# Debug.net
KiCad netlist of a schematic drawn in EAGLE
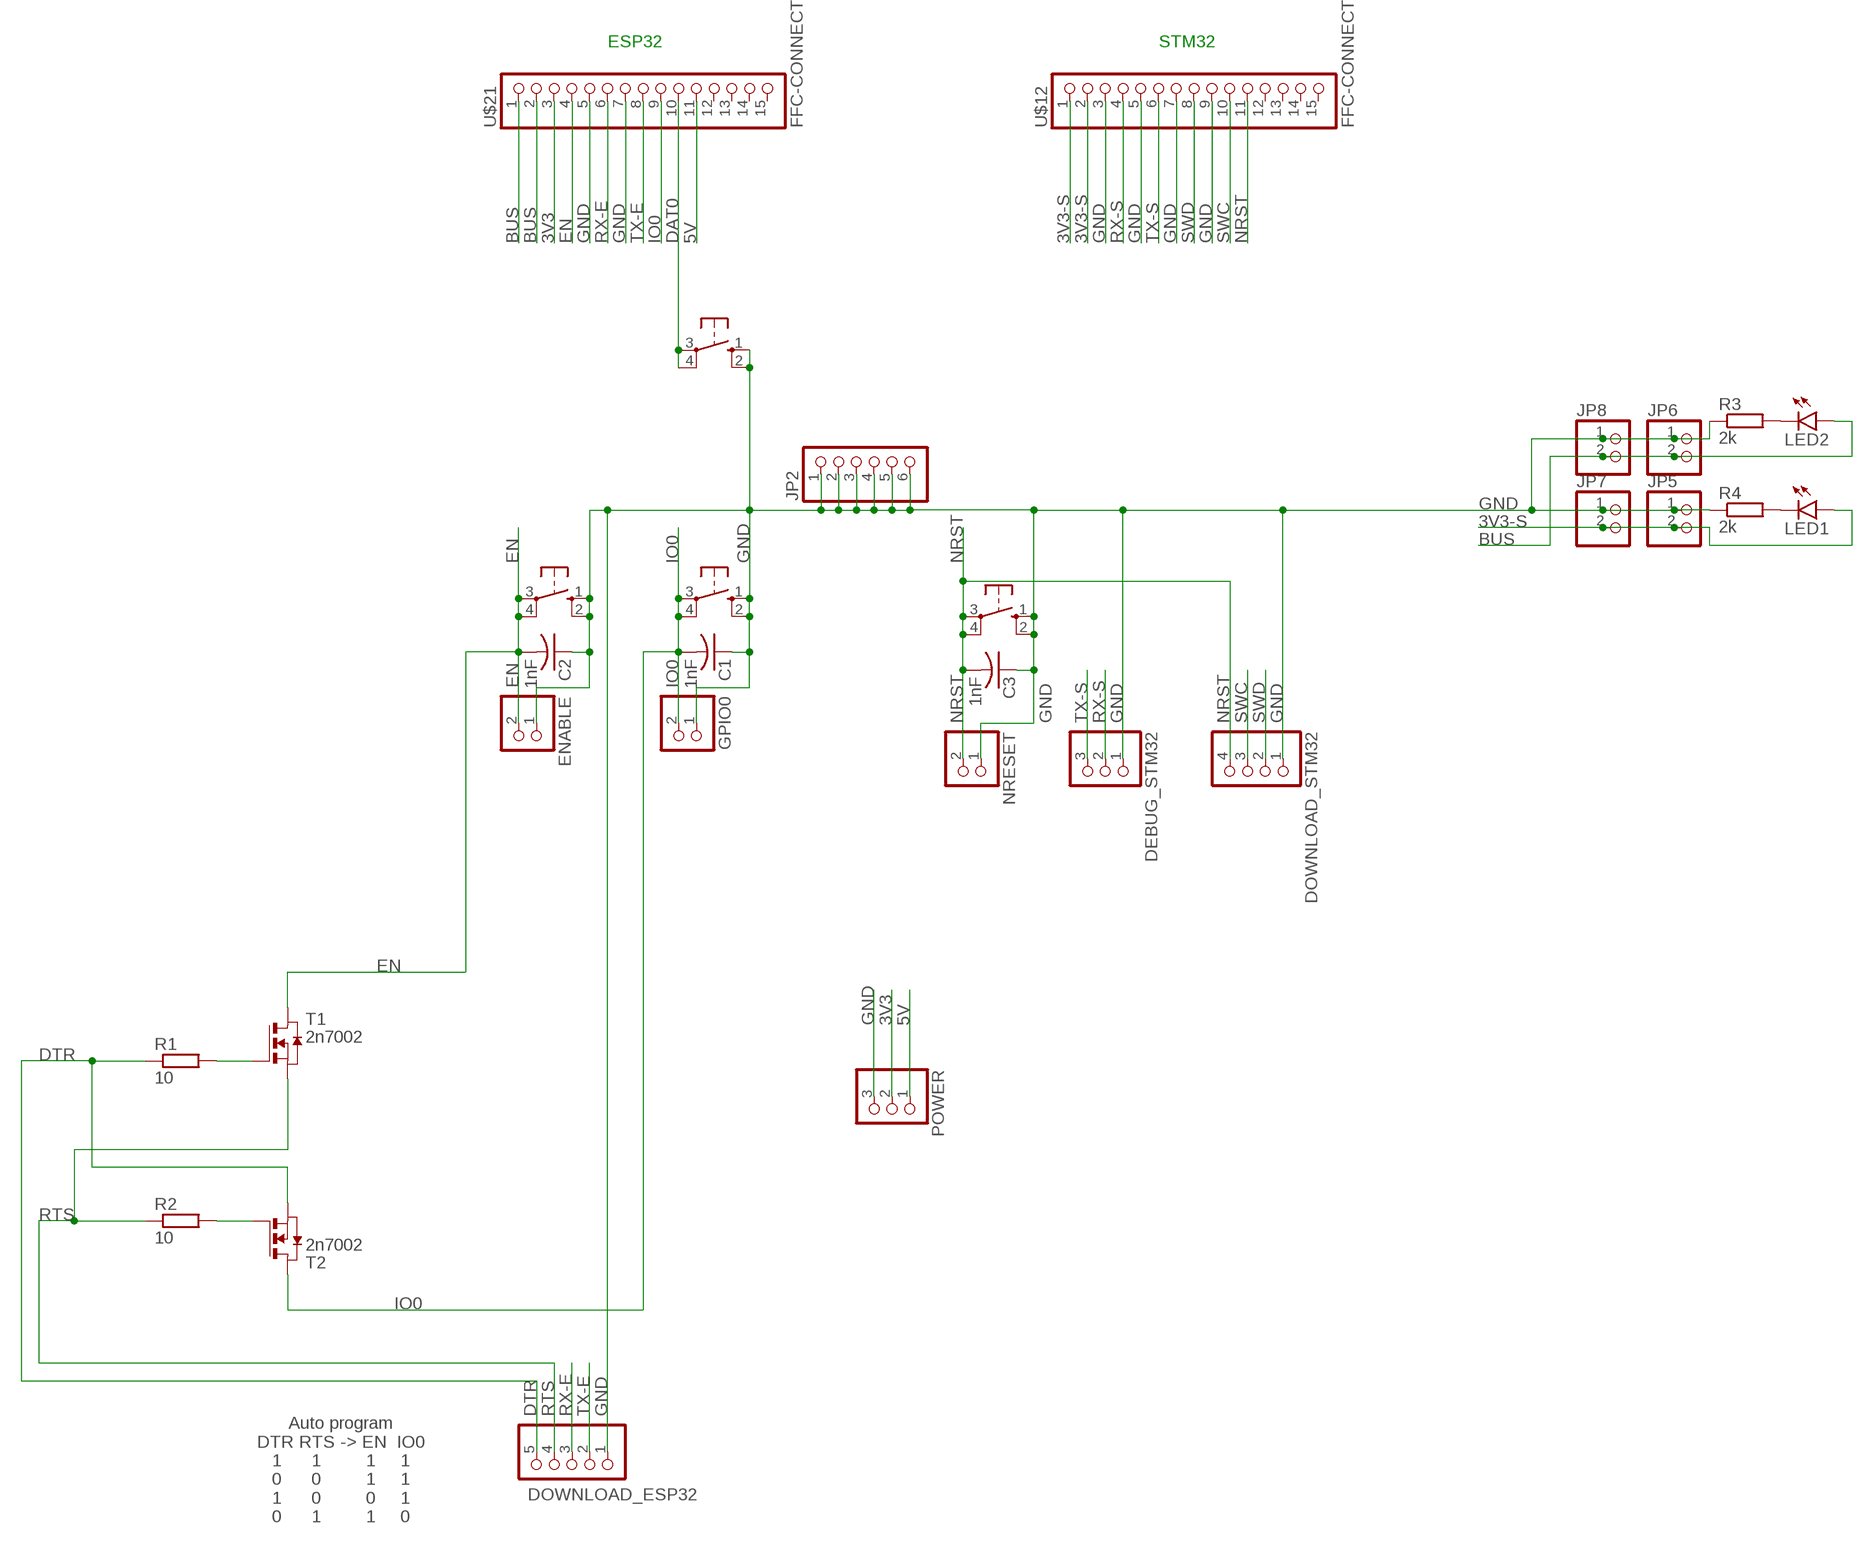
[diagram p0: schematic, sheet 1]

(export (version "E")
  (design (tool "Eeschema 10.0.6"))
  (components
    (comp (ref "C1")
      (value "1nF")
      (footprint "eagle-import:C0603")
      (libsource (lib "eagle-import") (part "C-USC0603"))
    )
    (comp (ref "C2")
      (value "1nF")
      (footprint "eagle-import:C0603")
      (libsource (lib "eagle-import") (part "C-USC0603"))
    )
    (comp (ref "C3")
      (value "1nF")
      (footprint "eagle-import:C0603")
      (libsource (lib "eagle-import") (part "C-USC0603"))
    )
    (comp (ref "DAT0")
      (value "10-XX")
      (footprint "eagle-import:B3F-10XX")
      (fields (field (name "MPN") "B3F-1000"))
      (libsource (lib "eagle-import") (part "10-XX"))
    )
    (comp (ref "DEBUG_STM32")
      (value "PINHD-1X3")
      (footprint "eagle-import:1X03")
      (libsource (lib "eagle-import") (part "PINHD-1X3"))
    )
    (comp (ref "DOWNLOAD_ESP32")
      (value "PINHD-1X5")
      (footprint "eagle-import:1X05")
      (libsource (lib "eagle-import") (part "PINHD-1X5"))
    )
    (comp (ref "DOWNLOAD_STM32")
      (value "PINHD-1X4")
      (footprint "eagle-import:1X04")
      (libsource (lib "eagle-import") (part "PINHD-1X4"))
    )
    (comp (ref "EN")
      (value "10-XX")
      (footprint "eagle-import:B3F-10XX")
      (fields (field (name "MPN") "B3F-1000"))
      (libsource (lib "eagle-import") (part "10-XX"))
    )
    (comp (ref "ENABLE")
      (value "PINHD-1X2")
      (footprint "eagle-import:1X02")
      (libsource (lib "eagle-import") (part "PINHD-1X2"))
    )
    (comp (ref "GPIO0")
      (value "PINHD-1X2")
      (footprint "eagle-import:1X02")
      (libsource (lib "eagle-import") (part "PINHD-1X2"))
    )
    (comp (ref "IO0")
      (value "10-XX")
      (footprint "eagle-import:B3F-10XX")
      (fields (field (name "MPN") "B3F-1000"))
      (libsource (lib "eagle-import") (part "10-XX"))
    )
    (comp (ref "JP2")
      (value "PINHD-1X6")
      (footprint "eagle-import:1X06")
      (libsource (lib "eagle-import") (part "PINHD-1X6"))
    )
    (comp (ref "JP5")
      (value "PINHD-1X2")
      (footprint "eagle-import:1X02")
      (libsource (lib "eagle-import") (part "PINHD-1X2"))
    )
    (comp (ref "JP6")
      (value "PINHD-1X2")
      (footprint "eagle-import:1X02")
      (libsource (lib "eagle-import") (part "PINHD-1X2"))
    )
    (comp (ref "JP7")
      (value "PINHD-1X2")
      (footprint "eagle-import:1X02")
      (libsource (lib "eagle-import") (part "PINHD-1X2"))
    )
    (comp (ref "JP8")
      (value "PINHD-1X2")
      (footprint "eagle-import:1X02")
      (libsource (lib "eagle-import") (part "PINHD-1X2"))
    )
    (comp (ref "LED1")
      (value "LEDCHIPLED_0603")
      (footprint "eagle-import:CHIPLED_0603")
      (libsource (lib "eagle-import") (part "LEDCHIPLED_0603"))
    )
    (comp (ref "LED2")
      (value "LEDCHIPLED_0603")
      (footprint "eagle-import:CHIPLED_0603")
      (libsource (lib "eagle-import") (part "LEDCHIPLED_0603"))
    )
    (comp (ref "NRESET")
      (value "PINHD-1X2")
      (footprint "eagle-import:1X02")
      (libsource (lib "eagle-import") (part "PINHD-1X2"))
    )
    (comp (ref "NRST")
      (value "10-XX")
      (footprint "eagle-import:B3F-10XX")
      (fields (field (name "MPN") "B3F-1000"))
      (libsource (lib "eagle-import") (part "10-XX"))
    )
    (comp (ref "POWER")
      (value "PINHD-1X3")
      (footprint "eagle-import:1X03")
      (libsource (lib "eagle-import") (part "PINHD-1X3"))
    )
    (comp (ref "R1")
      (value "10")
      (footprint "eagle-import:R0603")
      (libsource (lib "eagle-import") (part "R-EU_R0603"))
    )
    (comp (ref "R2")
      (value "10")
      (footprint "eagle-import:R0603")
      (libsource (lib "eagle-import") (part "R-EU_R0603"))
    )
    (comp (ref "R3")
      (value "2k")
      (footprint "eagle-import:R0603")
      (libsource (lib "eagle-import") (part "R-EU_R0603"))
    )
    (comp (ref "R4")
      (value "2k")
      (footprint "eagle-import:R0603")
      (libsource (lib "eagle-import") (part "R-EU_R0603"))
    )
    (comp (ref "T1")
      (value "2n7002")
      (footprint "eagle-import:SOT-23")
      (libsource (lib "eagle-import") (part "NMOSSOT23"))
    )
    (comp (ref "T2")
      (value "2n7002")
      (footprint "eagle-import:SOT-23")
      (libsource (lib "eagle-import") (part "NMOSSOT23"))
    )
    (comp (ref "U$12")
      (value "FFC-CONNECT")
      (footprint "eagle-import:SLW15S")
      (libsource (lib "eagle-import") (part "FFC-CONNECT"))
    )
    (comp (ref "U$21")
      (value "FFC-CONNECT")
      (footprint "eagle-import:SLW15S")
      (libsource (lib "eagle-import") (part "FFC-CONNECT"))
    )
  )
  (nets
    (net (code "1") (name "/3V3") (class "Default")
      (node (ref "POWER") (pin "2") (pinfunction "2_2") (pintype "passive"))
      (node (ref "U$21") (pin "3") (pinfunction "3_3") (pintype "passive"))
    )
    (net (code "2") (name "/3V3-S") (class "Default")
      (node (ref "JP5") (pin "2") (pinfunction "2_2") (pintype "passive"))
      (node (ref "JP7") (pin "2") (pinfunction "2_2") (pintype "passive"))
      (node (ref "LED1") (pin "A") (pinfunction "A_A") (pintype "passive"))
      (node (ref "U$12") (pin "1") (pinfunction "1_1") (pintype "passive"))
      (node (ref "U$12") (pin "2") (pinfunction "2_2") (pintype "passive"))
    )
    (net (code "3") (name "/5V") (class "Default")
      (node (ref "POWER") (pin "1") (pinfunction "1_1") (pintype "passive"))
      (node (ref "U$21") (pin "11") (pinfunction "11_11") (pintype "passive"))
    )
    (net (code "4") (name "/BUS") (class "Default")
      (node (ref "JP6") (pin "2") (pinfunction "2_2") (pintype "passive"))
      (node (ref "JP8") (pin "2") (pinfunction "2_2") (pintype "passive"))
      (node (ref "LED2") (pin "A") (pinfunction "A_A") (pintype "passive"))
      (node (ref "U$21") (pin "1") (pinfunction "1_1") (pintype "passive"))
      (node (ref "U$21") (pin "2") (pinfunction "2_2") (pintype "passive"))
    )
    (net (code "5") (name "/DAT0") (class "Default")
      (node (ref "DAT0") (pin "3") (pinfunction "P_3") (pintype "passive"))
      (node (ref "DAT0") (pin "4") (pinfunction "P1_4") (pintype "passive"))
      (node (ref "U$21") (pin "10") (pinfunction "10_10") (pintype "passive"))
    )
    (net (code "6") (name "/DTR") (class "Default")
      (node (ref "DOWNLOAD_ESP32") (pin "5") (pinfunction "5_5") (pintype "passive"))
      (node (ref "R1") (pin "1") (pinfunction "1_1") (pintype "passive"))
      (node (ref "T2") (pin "2") (pinfunction "S_2") (pintype "passive"))
    )
    (net (code "7") (name "/EN") (class "Default")
      (node (ref "C2") (pin "2") (pinfunction "2_2") (pintype "passive"))
      (node (ref "EN") (pin "3") (pinfunction "P_3") (pintype "passive"))
      (node (ref "EN") (pin "4") (pinfunction "P1_4") (pintype "passive"))
      (node (ref "ENABLE") (pin "2") (pinfunction "2_2") (pintype "passive"))
      (node (ref "T1") (pin "1") (pinfunction "D_1") (pintype "passive"))
      (node (ref "U$21") (pin "4") (pinfunction "4_4") (pintype "passive"))
    )
    (net (code "8") (name "/GND") (class "Default")
      (node (ref "C1") (pin "1") (pinfunction "1_1") (pintype "passive"))
      (node (ref "C2") (pin "1") (pinfunction "1_1") (pintype "passive"))
      (node (ref "C3") (pin "1") (pinfunction "1_1") (pintype "passive"))
      (node (ref "DAT0") (pin "1") (pinfunction "S_1") (pintype "passive"))
      (node (ref "DAT0") (pin "2") (pinfunction "S1_2") (pintype "passive"))
      (node (ref "DEBUG_STM32") (pin "1") (pinfunction "1_1") (pintype "passive"))
      (node (ref "DOWNLOAD_ESP32") (pin "1") (pinfunction "1_1") (pintype "passive"))
      (node (ref "DOWNLOAD_STM32") (pin "1") (pinfunction "1_1") (pintype "passive"))
      (node (ref "EN") (pin "1") (pinfunction "S_1") (pintype "passive"))
      (node (ref "EN") (pin "2") (pinfunction "S1_2") (pintype "passive"))
      (node (ref "ENABLE") (pin "1") (pinfunction "1_1") (pintype "passive"))
      (node (ref "GPIO0") (pin "1") (pinfunction "1_1") (pintype "passive"))
      (node (ref "IO0") (pin "1") (pinfunction "S_1") (pintype "passive"))
      (node (ref "IO0") (pin "2") (pinfunction "S1_2") (pintype "passive"))
      (node (ref "JP2") (pin "1") (pinfunction "1_1") (pintype "passive"))
      (node (ref "JP2") (pin "2") (pinfunction "2_2") (pintype "passive"))
      (node (ref "JP2") (pin "3") (pinfunction "3_3") (pintype "passive"))
      (node (ref "JP2") (pin "4") (pinfunction "4_4") (pintype "passive"))
      (node (ref "JP2") (pin "5") (pinfunction "5_5") (pintype "passive"))
      (node (ref "JP2") (pin "6") (pinfunction "6_6") (pintype "passive"))
      (node (ref "JP5") (pin "1") (pinfunction "1_1") (pintype "passive"))
      (node (ref "JP6") (pin "1") (pinfunction "1_1") (pintype "passive"))
      (node (ref "JP7") (pin "1") (pinfunction "1_1") (pintype "passive"))
      (node (ref "JP8") (pin "1") (pinfunction "1_1") (pintype "passive"))
      (node (ref "NRESET") (pin "1") (pinfunction "1_1") (pintype "passive"))
      (node (ref "NRST") (pin "1") (pinfunction "S_1") (pintype "passive"))
      (node (ref "NRST") (pin "2") (pinfunction "S1_2") (pintype "passive"))
      (node (ref "POWER") (pin "3") (pinfunction "3_3") (pintype "passive"))
      (node (ref "R3") (pin "1") (pinfunction "1_1") (pintype "passive"))
      (node (ref "R4") (pin "1") (pinfunction "1_1") (pintype "passive"))
      (node (ref "U$12") (pin "3") (pinfunction "3_3") (pintype "passive"))
      (node (ref "U$12") (pin "5") (pinfunction "5_5") (pintype "passive"))
      (node (ref "U$12") (pin "7") (pinfunction "7_7") (pintype "passive"))
      (node (ref "U$12") (pin "9") (pinfunction "9_9") (pintype "passive"))
      (node (ref "U$21") (pin "5") (pinfunction "5_5") (pintype "passive"))
      (node (ref "U$21") (pin "7") (pinfunction "7_7") (pintype "passive"))
    )
    (net (code "9") (name "/IO0") (class "Default")
      (node (ref "C1") (pin "2") (pinfunction "2_2") (pintype "passive"))
      (node (ref "GPIO0") (pin "2") (pinfunction "2_2") (pintype "passive"))
      (node (ref "IO0") (pin "3") (pinfunction "P_3") (pintype "passive"))
      (node (ref "IO0") (pin "4") (pinfunction "P1_4") (pintype "passive"))
      (node (ref "T2") (pin "1") (pinfunction "D_1") (pintype "passive"))
      (node (ref "U$21") (pin "9") (pinfunction "9_9") (pintype "passive"))
    )
    (net (code "10") (name "/NRST") (class "Default")
      (node (ref "C3") (pin "2") (pinfunction "2_2") (pintype "passive"))
      (node (ref "DOWNLOAD_STM32") (pin "4") (pinfunction "4_4") (pintype "passive"))
      (node (ref "NRESET") (pin "2") (pinfunction "2_2") (pintype "passive"))
      (node (ref "NRST") (pin "3") (pinfunction "P_3") (pintype "passive"))
      (node (ref "NRST") (pin "4") (pinfunction "P1_4") (pintype "passive"))
      (node (ref "U$12") (pin "11") (pinfunction "11_11") (pintype "passive"))
    )
    (net (code "11") (name "/RTS") (class "Default")
      (node (ref "DOWNLOAD_ESP32") (pin "4") (pinfunction "4_4") (pintype "passive"))
      (node (ref "R2") (pin "1") (pinfunction "1_1") (pintype "passive"))
      (node (ref "T1") (pin "2") (pinfunction "S_2") (pintype "passive"))
    )
    (net (code "12") (name "/RX-E") (class "Default")
      (node (ref "DOWNLOAD_ESP32") (pin "3") (pinfunction "3_3") (pintype "passive"))
      (node (ref "U$21") (pin "6") (pinfunction "6_6") (pintype "passive"))
    )
    (net (code "13") (name "/RX-S") (class "Default")
      (node (ref "DEBUG_STM32") (pin "2") (pinfunction "2_2") (pintype "passive"))
      (node (ref "U$12") (pin "4") (pinfunction "4_4") (pintype "passive"))
    )
    (net (code "14") (name "/SWC") (class "Default")
      (node (ref "DOWNLOAD_STM32") (pin "3") (pinfunction "3_3") (pintype "passive"))
      (node (ref "U$12") (pin "10") (pinfunction "10_10") (pintype "passive"))
    )
    (net (code "15") (name "/SWD") (class "Default")
      (node (ref "DOWNLOAD_STM32") (pin "2") (pinfunction "2_2") (pintype "passive"))
      (node (ref "U$12") (pin "8") (pinfunction "8_8") (pintype "passive"))
    )
    (net (code "16") (name "/TX-E") (class "Default")
      (node (ref "DOWNLOAD_ESP32") (pin "2") (pinfunction "2_2") (pintype "passive"))
      (node (ref "U$21") (pin "8") (pinfunction "8_8") (pintype "passive"))
    )
    (net (code "17") (name "/TX-S") (class "Default")
      (node (ref "DEBUG_STM32") (pin "3") (pinfunction "3_3") (pintype "passive"))
      (node (ref "U$12") (pin "6") (pinfunction "6_6") (pintype "passive"))
    )
    (net (code "18") (name "Net-(LED1-PadC)") (class "Default")
      (node (ref "LED1") (pin "C") (pinfunction "C_C") (pintype "passive"))
      (node (ref "R4") (pin "2") (pinfunction "2_2") (pintype "passive"))
    )
    (net (code "19") (name "Net-(LED2-PadC)") (class "Default")
      (node (ref "LED2") (pin "C") (pinfunction "C_C") (pintype "passive"))
      (node (ref "R3") (pin "2") (pinfunction "2_2") (pintype "passive"))
    )
    (net (code "20") (name "Net-(T1-G)") (class "Default")
      (node (ref "R1") (pin "2") (pinfunction "2_2") (pintype "passive"))
      (node (ref "T1") (pin "3") (pinfunction "G_3") (pintype "passive"))
    )
    (net (code "21") (name "Net-(T2-G)") (class "Default")
      (node (ref "R2") (pin "2") (pinfunction "2_2") (pintype "passive"))
      (node (ref "T2") (pin "3") (pinfunction "G_3") (pintype "passive"))
    )
    (net (code "22") (name "unconnected-(U$12-Pad12)") (class "Default")
      (node (ref "U$12") (pin "12") (pinfunction "12_12") (pintype "passive"))
    )
    (net (code "23") (name "unconnected-(U$12-Pad13)") (class "Default")
      (node (ref "U$12") (pin "13") (pinfunction "13_13") (pintype "passive"))
    )
    (net (code "24") (name "unconnected-(U$12-Pad14)") (class "Default")
      (node (ref "U$12") (pin "14") (pinfunction "14_14") (pintype "passive"))
    )
    (net (code "25") (name "unconnected-(U$12-Pad15)") (class "Default")
      (node (ref "U$12") (pin "15") (pinfunction "15_15") (pintype "passive"))
    )
    (net (code "26") (name "unconnected-(U$21-Pad12)") (class "Default")
      (node (ref "U$21") (pin "12") (pinfunction "12_12") (pintype "passive"))
    )
    (net (code "27") (name "unconnected-(U$21-Pad13)") (class "Default")
      (node (ref "U$21") (pin "13") (pinfunction "13_13") (pintype "passive"))
    )
    (net (code "28") (name "unconnected-(U$21-Pad14)") (class "Default")
      (node (ref "U$21") (pin "14") (pinfunction "14_14") (pintype "passive"))
    )
    (net (code "29") (name "unconnected-(U$21-Pad15)") (class "Default")
      (node (ref "U$21") (pin "15") (pinfunction "15_15") (pintype "passive"))
    )
  )
)
